# takujou_memo.net
KiCad netlist of a schematic drawn in EAGLE
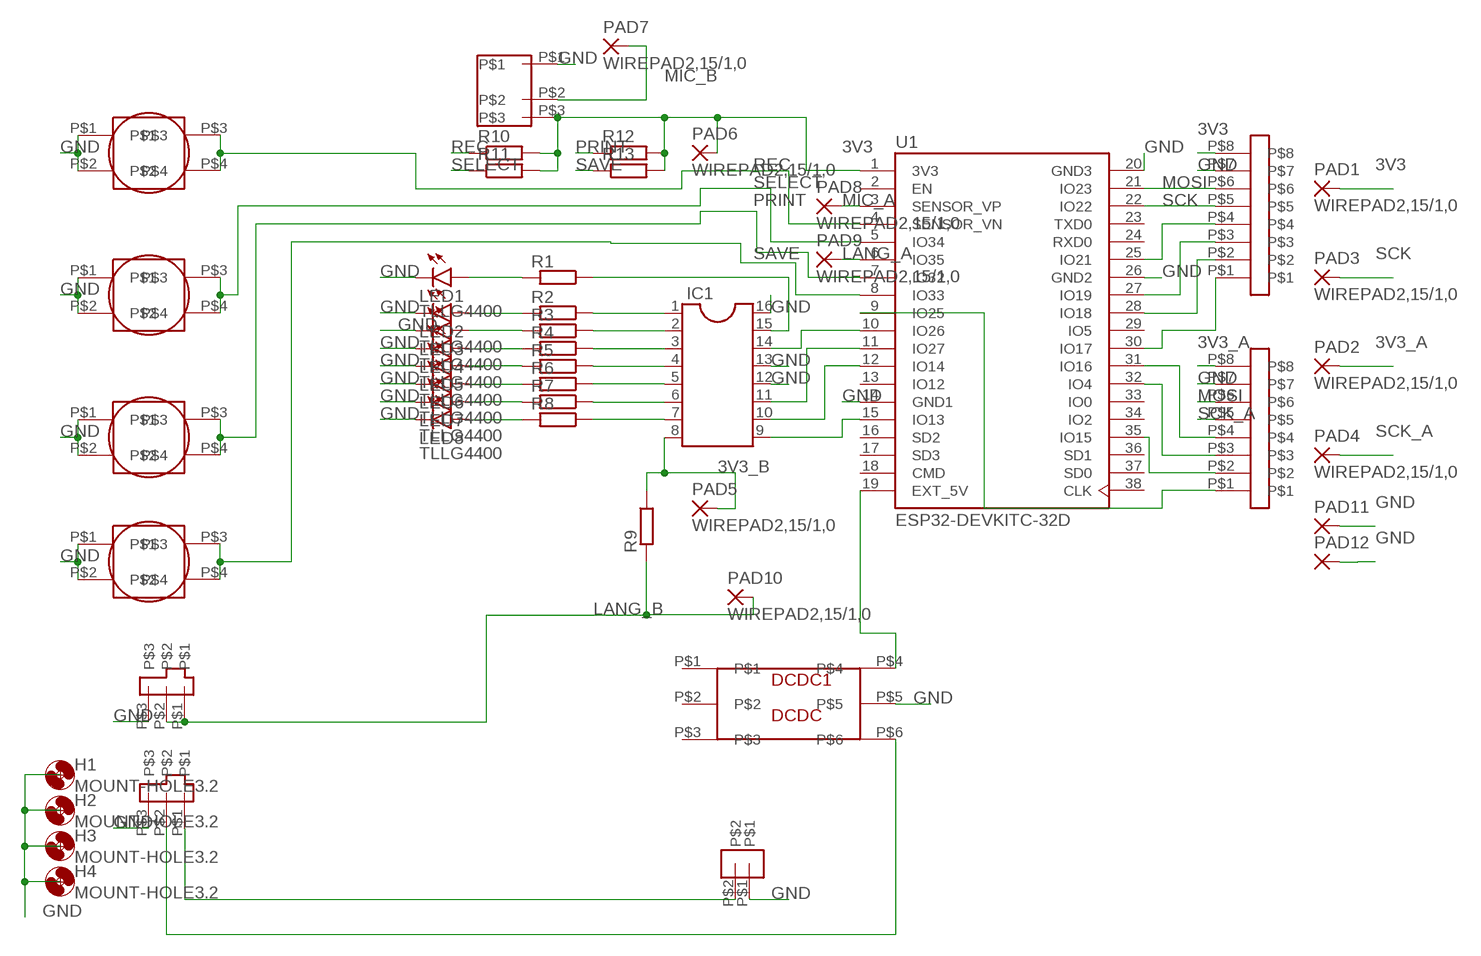
[diagram p0: schematic, sheet 1]

(export (version "E")
  (design (tool "Eeschema 10.0.6"))
  (components
    (comp (ref "BATTERY1")
      (value "BATTERY")
      (footprint "eagle-import:BATTERY")
      (libsource (lib "eagle-import") (part "BATTERY"))
    )
    (comp (ref "DCDC1")
      (value "DCDC")
      (footprint "eagle-import:DCDC")
      (libsource (lib "eagle-import") (part "DCDC"))
    )
    (comp (ref "DISPLAY1")
      (value "DISPLAY")
      (footprint "eagle-import:DISPLAY")
      (libsource (lib "eagle-import") (part "DISPLAY"))
    )
    (comp (ref "DISPLAY2")
      (value "DISPLAY")
      (footprint "eagle-import:DISPLAY")
      (libsource (lib "eagle-import") (part "DISPLAY"))
    )
    (comp (ref "H1")
      (value "MOUNT-HOLE3.2")
      (footprint "eagle-import:3,2")
      (libsource (lib "eagle-import") (part "MOUNT-HOLE3.2"))
    )
    (comp (ref "H2")
      (value "MOUNT-HOLE3.2")
      (footprint "eagle-import:3,2")
      (libsource (lib "eagle-import") (part "MOUNT-HOLE3.2"))
    )
    (comp (ref "H3")
      (value "MOUNT-HOLE3.2")
      (footprint "eagle-import:3,2")
      (libsource (lib "eagle-import") (part "MOUNT-HOLE3.2"))
    )
    (comp (ref "H4")
      (value "MOUNT-HOLE3.2")
      (footprint "eagle-import:3,2")
      (libsource (lib "eagle-import") (part "MOUNT-HOLE3.2"))
    )
    (comp (ref "IC1")
      (value "DIL16S")
      (footprint "eagle-import:SOCKET-16")
      (libsource (lib "eagle-import") (part "DIL16S"))
    )
    (comp (ref "LED1")
      (value "TLLG4400")
      (footprint "eagle-import:LED3MM")
      (fields (field (name "MF") "VISHAY SEMICONDUCTOR"))
      (libsource (lib "eagle-import") (part "TLLG4400"))
    )
    (comp (ref "LED2")
      (value "TLLG4400")
      (footprint "eagle-import:LED3MM")
      (fields (field (name "MF") "VISHAY SEMICONDUCTOR"))
      (libsource (lib "eagle-import") (part "TLLG4400"))
    )
    (comp (ref "LED3")
      (value "TLLG4400")
      (footprint "eagle-import:LED3MM")
      (fields (field (name "MF") "VISHAY SEMICONDUCTOR"))
      (libsource (lib "eagle-import") (part "TLLG4400"))
    )
    (comp (ref "LED4")
      (value "TLLG4400")
      (footprint "eagle-import:LED3MM")
      (fields (field (name "MF") "VISHAY SEMICONDUCTOR"))
      (libsource (lib "eagle-import") (part "TLLG4400"))
    )
    (comp (ref "LED5")
      (value "TLLG4400")
      (footprint "eagle-import:LED3MM")
      (fields (field (name "MF") "VISHAY SEMICONDUCTOR"))
      (libsource (lib "eagle-import") (part "TLLG4400"))
    )
    (comp (ref "LED6")
      (value "TLLG4400")
      (footprint "eagle-import:LED3MM")
      (fields (field (name "MF") "VISHAY SEMICONDUCTOR"))
      (libsource (lib "eagle-import") (part "TLLG4400"))
    )
    (comp (ref "LED7")
      (value "TLLG4400")
      (footprint "eagle-import:LED3MM")
      (fields (field (name "MF") "VISHAY SEMICONDUCTOR"))
      (libsource (lib "eagle-import") (part "TLLG4400"))
    )
    (comp (ref "LED8")
      (value "TLLG4400")
      (footprint "eagle-import:LED3MM")
      (fields (field (name "MF") "VISHAY SEMICONDUCTOR"))
      (libsource (lib "eagle-import") (part "TLLG4400"))
    )
    (comp (ref "MIC1")
      (value "MIC")
      (footprint "eagle-import:MIC")
      (libsource (lib "eagle-import") (part "MIC"))
    )
    (comp (ref "PAD1")
      (value "WIREPAD2,15/1,0")
      (footprint "eagle-import:2,15_1,0")
      (libsource (lib "eagle-import") (part "WIREPAD2,15/1,0"))
    )
    (comp (ref "PAD2")
      (value "WIREPAD2,15/1,0")
      (footprint "eagle-import:2,15_1,0")
      (libsource (lib "eagle-import") (part "WIREPAD2,15/1,0"))
    )
    (comp (ref "PAD3")
      (value "WIREPAD2,15/1,0")
      (footprint "eagle-import:2,15_1,0")
      (libsource (lib "eagle-import") (part "WIREPAD2,15/1,0"))
    )
    (comp (ref "PAD4")
      (value "WIREPAD2,15/1,0")
      (footprint "eagle-import:2,15_1,0")
      (libsource (lib "eagle-import") (part "WIREPAD2,15/1,0"))
    )
    (comp (ref "PAD5")
      (value "WIREPAD2,15/1,0")
      (footprint "eagle-import:2,15_1,0")
      (libsource (lib "eagle-import") (part "WIREPAD2,15/1,0"))
    )
    (comp (ref "PAD6")
      (value "WIREPAD2,15/1,0")
      (footprint "eagle-import:2,15_1,0")
      (libsource (lib "eagle-import") (part "WIREPAD2,15/1,0"))
    )
    (comp (ref "PAD7")
      (value "WIREPAD2,15/1,0")
      (footprint "eagle-import:2,15_1,0")
      (libsource (lib "eagle-import") (part "WIREPAD2,15/1,0"))
    )
    (comp (ref "PAD8")
      (value "WIREPAD2,15/1,0")
      (footprint "eagle-import:2,15_1,0")
      (libsource (lib "eagle-import") (part "WIREPAD2,15/1,0"))
    )
    (comp (ref "PAD9")
      (value "WIREPAD2,15/1,0")
      (footprint "eagle-import:2,15_1,0")
      (libsource (lib "eagle-import") (part "WIREPAD2,15/1,0"))
    )
    (comp (ref "PAD10")
      (value "WIREPAD2,15/1,0")
      (footprint "eagle-import:2,15_1,0")
      (libsource (lib "eagle-import") (part "WIREPAD2,15/1,0"))
    )
    (comp (ref "PAD11")
      (value "2,15/1,0")
      (footprint "eagle-import:2,15_1,0")
      (libsource (lib "eagle-import") (part "2,15/1,0"))
    )
    (comp (ref "PAD12")
      (value "2,15/1,0")
      (footprint "eagle-import:2,15_1,0")
      (libsource (lib "eagle-import") (part "2,15/1,0"))
    )
    (comp (ref "R1")
      (value "SMK")
      (footprint "eagle-import:SMK")
      (libsource (lib "eagle-import") (part "SMK"))
    )
    (comp (ref "R2")
      (value "SMK")
      (footprint "eagle-import:SMK")
      (libsource (lib "eagle-import") (part "SMK"))
    )
    (comp (ref "R3")
      (value "SMK")
      (footprint "eagle-import:SMK")
      (libsource (lib "eagle-import") (part "SMK"))
    )
    (comp (ref "R4")
      (value "SMK")
      (footprint "eagle-import:SMK")
      (libsource (lib "eagle-import") (part "SMK"))
    )
    (comp (ref "R5")
      (value "SMK")
      (footprint "eagle-import:SMK")
      (libsource (lib "eagle-import") (part "SMK"))
    )
    (comp (ref "R6")
      (value "SMK")
      (footprint "eagle-import:SMK")
      (libsource (lib "eagle-import") (part "SMK"))
    )
    (comp (ref "R7")
      (value "SMK")
      (footprint "eagle-import:SMK")
      (libsource (lib "eagle-import") (part "SMK"))
    )
    (comp (ref "R8")
      (value "SMK")
      (footprint "eagle-import:SMK")
      (libsource (lib "eagle-import") (part "SMK"))
    )
    (comp (ref "R9")
      (value "SMK")
      (footprint "eagle-import:SMK")
      (libsource (lib "eagle-import") (part "SMK"))
    )
    (comp (ref "R10")
      (value "R-EU_0207/10")
      (footprint "eagle-import:0207_10")
      (libsource (lib "eagle-import") (part "R-EU_0207/10"))
    )
    (comp (ref "R11")
      (value "R-EU_0207/10")
      (footprint "eagle-import:0207_10")
      (libsource (lib "eagle-import") (part "R-EU_0207/10"))
    )
    (comp (ref "R12")
      (value "R-EU_0207/10")
      (footprint "eagle-import:0207_10")
      (libsource (lib "eagle-import") (part "R-EU_0207/10"))
    )
    (comp (ref "R13")
      (value "R-EU_0207/10")
      (footprint "eagle-import:0207_10")
      (libsource (lib "eagle-import") (part "R-EU_0207/10"))
    )
    (comp (ref "SWITCH1")
      (value "SWITCH")
      (footprint "eagle-import:SWITCH")
      (libsource (lib "eagle-import") (part "SWITCH"))
    )
    (comp (ref "SWITCH2")
      (value "SWITCH")
      (footprint "eagle-import:SWITCH")
      (libsource (lib "eagle-import") (part "SWITCH"))
    )
    (comp (ref "SWITCH3")
      (value "SWITCH")
      (footprint "eagle-import:SWITCH")
      (libsource (lib "eagle-import") (part "SWITCH"))
    )
    (comp (ref "SWITCH4")
      (value "SWITCH")
      (footprint "eagle-import:SWITCH")
      (libsource (lib "eagle-import") (part "SWITCH"))
    )
    (comp (ref "TOGGLE1")
      (value "TOGGLE")
      (footprint "eagle-import:TOGGLE")
      (libsource (lib "eagle-import") (part "TOGGLE"))
    )
    (comp (ref "TOGGLE2")
      (value "TOGGLE")
      (footprint "eagle-import:TOGGLE")
      (libsource (lib "eagle-import") (part "TOGGLE"))
    )
    (comp (ref "U1")
      (value "ESP32-DEVKITC-32D")
      (footprint "eagle-import:MODULE_ESP32-DEVKITC-32D")
      (fields (field (name "MF") "Espressif Systems"))
      (libsource (lib "eagle-import") (part "ESP32-DEVKITC-32D"))
    )
  )
  (nets
    (net (code "1") (name "/3V3") (class "Default")
      (node (ref "DISPLAY1") (pin "P$8") (pinfunction "P$8_P$8") (pintype "bidirectional"))
      (node (ref "MIC1") (pin "P$3") (pinfunction "P$3_P$3") (pintype "bidirectional"))
      (node (ref "PAD1") (pin "1") (pinfunction "P_1") (pintype "passive"))
      (node (ref "PAD6") (pin "1") (pinfunction "P_1") (pintype "passive"))
      (node (ref "R10") (pin "2") (pinfunction "2_2") (pintype "passive"))
      (node (ref "R11") (pin "2") (pinfunction "2_2") (pintype "passive"))
      (node (ref "R12") (pin "2") (pinfunction "2_2") (pintype "passive"))
      (node (ref "R13") (pin "2") (pinfunction "2_2") (pintype "passive"))
      (node (ref "U1") (pin "1") (pinfunction "3V3_1") (pintype "power_in"))
    )
    (net (code "2") (name "/3V3_A") (class "Default")
      (node (ref "DISPLAY2") (pin "P$8") (pinfunction "P$8_P$8") (pintype "bidirectional"))
      (node (ref "PAD2") (pin "1") (pinfunction "P_1") (pintype "passive"))
    )
    (net (code "3") (name "/3V3_B") (class "Default")
      (node (ref "IC1") (pin "8") (pinfunction "8_8") (pintype "passive"))
      (node (ref "PAD5") (pin "1") (pinfunction "P_1") (pintype "passive"))
      (node (ref "R9") (pin "1") (pinfunction "1_1") (pintype "passive"))
    )
    (net (code "4") (name "/GND") (class "Default")
      (node (ref "BATTERY1") (pin "P$1") (pinfunction "P$1_P$1") (pintype "bidirectional"))
      (node (ref "DCDC1") (pin "P$5") (pinfunction "P$5_P$5") (pintype "bidirectional"))
      (node (ref "DISPLAY1") (pin "P$7") (pinfunction "P$7_P$7") (pintype "bidirectional"))
      (node (ref "DISPLAY2") (pin "P$7") (pinfunction "P$7_P$7") (pintype "bidirectional"))
      (node (ref "IC1") (pin "12") (pinfunction "12_12") (pintype "passive"))
      (node (ref "IC1") (pin "13") (pinfunction "13_13") (pintype "passive"))
      (node (ref "IC1") (pin "16") (pinfunction "16_16") (pintype "passive"))
      (node (ref "LED1") (pin "K") (pinfunction "C_K") (pintype "passive"))
      (node (ref "LED2") (pin "K") (pinfunction "C_K") (pintype "passive"))
      (node (ref "LED3") (pin "K") (pinfunction "C_K") (pintype "passive"))
      (node (ref "LED4") (pin "K") (pinfunction "C_K") (pintype "passive"))
      (node (ref "LED5") (pin "K") (pinfunction "C_K") (pintype "passive"))
      (node (ref "LED6") (pin "K") (pinfunction "C_K") (pintype "passive"))
      (node (ref "LED7") (pin "K") (pinfunction "C_K") (pintype "passive"))
      (node (ref "LED8") (pin "K") (pinfunction "C_K") (pintype "passive"))
      (node (ref "MIC1") (pin "P$1") (pinfunction "P$1_P$1") (pintype "bidirectional"))
      (node (ref "PAD11") (pin "1") (pinfunction "P_1") (pintype "passive"))
      (node (ref "PAD12") (pin "1") (pinfunction "P_1") (pintype "passive"))
      (node (ref "SWITCH1") (pin "P$1") (pinfunction "P$1_P$1") (pintype "bidirectional"))
      (node (ref "SWITCH1") (pin "P$2") (pinfunction "P$2_P$2") (pintype "bidirectional"))
      (node (ref "SWITCH2") (pin "P$1") (pinfunction "P$1_P$1") (pintype "bidirectional"))
      (node (ref "SWITCH2") (pin "P$2") (pinfunction "P$2_P$2") (pintype "bidirectional"))
      (node (ref "SWITCH3") (pin "P$1") (pinfunction "P$1_P$1") (pintype "bidirectional"))
      (node (ref "SWITCH3") (pin "P$2") (pinfunction "P$2_P$2") (pintype "bidirectional"))
      (node (ref "SWITCH4") (pin "P$1") (pinfunction "P$1_P$1") (pintype "bidirectional"))
      (node (ref "SWITCH4") (pin "P$2") (pinfunction "P$2_P$2") (pintype "bidirectional"))
      (node (ref "TOGGLE1") (pin "P$3") (pinfunction "P$3_P$3") (pintype "bidirectional"))
      (node (ref "TOGGLE2") (pin "P$3") (pinfunction "P$3_P$3") (pintype "bidirectional"))
      (node (ref "U1") (pin "14") (pinfunction "GND1_14") (pintype "power_in"))
      (node (ref "U1") (pin "20") (pinfunction "GND3_20") (pintype "power_in"))
      (node (ref "U1") (pin "26") (pinfunction "GND2_26") (pintype "power_in"))
    )
    (net (code "5") (name "/LANG_A") (class "Default")
      (node (ref "PAD9") (pin "1") (pinfunction "P_1") (pintype "passive"))
      (node (ref "U1") (pin "6") (pinfunction "IO35_6") (pintype "bidirectional"))
    )
    (net (code "6") (name "/LANG_B") (class "Default")
      (node (ref "PAD10") (pin "1") (pinfunction "P_1") (pintype "passive"))
      (node (ref "R9") (pin "2") (pinfunction "2_2") (pintype "passive"))
      (node (ref "TOGGLE1") (pin "P$1") (pinfunction "P$1_P$1") (pintype "bidirectional"))
      (node (ref "TOGGLE1") (pin "P$2") (pinfunction "P$2_P$2") (pintype "bidirectional"))
    )
    (net (code "7") (name "/MIC_A") (class "Default")
      (node (ref "PAD8") (pin "1") (pinfunction "P_1") (pintype "passive"))
      (node (ref "U1") (pin "3") (pinfunction "SENSOR_VP_3") (pintype "input"))
    )
    (net (code "8") (name "/MIC_B") (class "Default")
      (node (ref "MIC1") (pin "P$2") (pinfunction "P$2_P$2") (pintype "bidirectional"))
      (node (ref "PAD7") (pin "1") (pinfunction "P_1") (pintype "passive"))
    )
    (net (code "9") (name "/MOSI") (class "Default")
      (node (ref "DISPLAY1") (pin "P$6") (pinfunction "P$6_P$6") (pintype "bidirectional"))
      (node (ref "DISPLAY2") (pin "P$6") (pinfunction "P$6_P$6") (pintype "bidirectional"))
      (node (ref "U1") (pin "21") (pinfunction "IO23_21") (pintype "bidirectional"))
    )
    (net (code "10") (name "/PRINT") (class "Default")
      (node (ref "R12") (pin "1") (pinfunction "1_1") (pintype "passive"))
      (node (ref "SWITCH3") (pin "P$3") (pinfunction "P$3_P$3") (pintype "bidirectional"))
      (node (ref "SWITCH3") (pin "P$4") (pinfunction "P$4_P$4") (pintype "bidirectional"))
      (node (ref "U1") (pin "7") (pinfunction "IO32_7") (pintype "bidirectional"))
    )
    (net (code "11") (name "/REC") (class "Default")
      (node (ref "R10") (pin "1") (pinfunction "1_1") (pintype "passive"))
      (node (ref "SWITCH1") (pin "P$3") (pinfunction "P$3_P$3") (pintype "bidirectional"))
      (node (ref "SWITCH1") (pin "P$4") (pinfunction "P$4_P$4") (pintype "bidirectional"))
      (node (ref "U1") (pin "4") (pinfunction "SENSOR_VN_4") (pintype "input"))
    )
    (net (code "12") (name "/SAVE") (class "Default")
      (node (ref "R13") (pin "1") (pinfunction "1_1") (pintype "passive"))
      (node (ref "SWITCH4") (pin "P$3") (pinfunction "P$3_P$3") (pintype "bidirectional"))
      (node (ref "SWITCH4") (pin "P$4") (pinfunction "P$4_P$4") (pintype "bidirectional"))
      (node (ref "U1") (pin "8") (pinfunction "IO33_8") (pintype "bidirectional"))
    )
    (net (code "13") (name "/SCK") (class "Default")
      (node (ref "DISPLAY1") (pin "P$5") (pinfunction "P$5_P$5") (pintype "bidirectional"))
      (node (ref "PAD3") (pin "1") (pinfunction "P_1") (pintype "passive"))
      (node (ref "U1") (pin "22") (pinfunction "IO22_22") (pintype "bidirectional"))
    )
    (net (code "14") (name "/SCK_A") (class "Default")
      (node (ref "DISPLAY2") (pin "P$5") (pinfunction "P$5_P$5") (pintype "bidirectional"))
      (node (ref "PAD4") (pin "1") (pinfunction "P_1") (pintype "passive"))
    )
    (net (code "15") (name "/SELECT") (class "Default")
      (node (ref "R11") (pin "1") (pinfunction "1_1") (pintype "passive"))
      (node (ref "SWITCH2") (pin "P$3") (pinfunction "P$3_P$3") (pintype "bidirectional"))
      (node (ref "SWITCH2") (pin "P$4") (pinfunction "P$4_P$4") (pintype "bidirectional"))
      (node (ref "U1") (pin "5") (pinfunction "IO34_5") (pintype "bidirectional"))
    )
    (net (code "16") (name "Net-(BATTERY1-PadP$2)") (class "Default")
      (node (ref "BATTERY1") (pin "P$2") (pinfunction "P$2_P$2") (pintype "bidirectional"))
      (node (ref "TOGGLE2") (pin "P$1") (pinfunction "P$1_P$1") (pintype "bidirectional"))
    )
    (net (code "17") (name "Net-(DCDC1-PadP$6)") (class "Default")
      (node (ref "DCDC1") (pin "P$6") (pinfunction "P$6_P$6") (pintype "bidirectional"))
      (node (ref "TOGGLE2") (pin "P$2") (pinfunction "P$2_P$2") (pintype "bidirectional"))
    )
    (net (code "18") (name "Net-(IC1-Pad1)") (class "Default")
      (node (ref "IC1") (pin "1") (pinfunction "1_1") (pintype "passive"))
      (node (ref "R2") (pin "1") (pinfunction "1_1") (pintype "passive"))
    )
    (net (code "19") (name "Net-(IC1-Pad2)") (class "Default")
      (node (ref "IC1") (pin "2") (pinfunction "2_2") (pintype "passive"))
      (node (ref "R3") (pin "1") (pinfunction "1_1") (pintype "passive"))
    )
    (net (code "20") (name "Net-(IC1-Pad3)") (class "Default")
      (node (ref "IC1") (pin "3") (pinfunction "3_3") (pintype "passive"))
      (node (ref "R4") (pin "1") (pinfunction "1_1") (pintype "passive"))
    )
    (net (code "21") (name "Net-(IC1-Pad4)") (class "Default")
      (node (ref "IC1") (pin "4") (pinfunction "4_4") (pintype "passive"))
      (node (ref "R5") (pin "1") (pinfunction "1_1") (pintype "passive"))
    )
    (net (code "22") (name "Net-(IC1-Pad5)") (class "Default")
      (node (ref "IC1") (pin "5") (pinfunction "5_5") (pintype "passive"))
      (node (ref "R6") (pin "1") (pinfunction "1_1") (pintype "passive"))
    )
    (net (code "23") (name "Net-(IC1-Pad6)") (class "Default")
      (node (ref "IC1") (pin "6") (pinfunction "6_6") (pintype "passive"))
      (node (ref "R7") (pin "1") (pinfunction "1_1") (pintype "passive"))
    )
    (net (code "24") (name "Net-(IC1-Pad7)") (class "Default")
      (node (ref "IC1") (pin "7") (pinfunction "7_7") (pintype "passive"))
      (node (ref "R8") (pin "1") (pinfunction "1_1") (pintype "passive"))
    )
    (net (code "25") (name "Net-(IC1-Pad15)") (class "Default")
      (node (ref "IC1") (pin "15") (pinfunction "15_15") (pintype "passive"))
      (node (ref "R1") (pin "1") (pinfunction "1_1") (pintype "passive"))
    )
    (net (code "26") (name "Net-(LED1-PadA)") (class "Default")
      (node (ref "LED1") (pin "A") (pinfunction "A_A") (pintype "passive"))
      (node (ref "R1") (pin "2") (pinfunction "2_2") (pintype "passive"))
    )
    (net (code "27") (name "Net-(LED2-PadA)") (class "Default")
      (node (ref "LED2") (pin "A") (pinfunction "A_A") (pintype "passive"))
      (node (ref "R2") (pin "2") (pinfunction "2_2") (pintype "passive"))
    )
    (net (code "28") (name "Net-(LED3-PadA)") (class "Default")
      (node (ref "LED3") (pin "A") (pinfunction "A_A") (pintype "passive"))
      (node (ref "R3") (pin "2") (pinfunction "2_2") (pintype "passive"))
    )
    (net (code "29") (name "Net-(LED4-PadA)") (class "Default")
      (node (ref "LED4") (pin "A") (pinfunction "A_A") (pintype "passive"))
      (node (ref "R4") (pin "2") (pinfunction "2_2") (pintype "passive"))
    )
    (net (code "30") (name "Net-(LED5-PadA)") (class "Default")
      (node (ref "LED5") (pin "A") (pinfunction "A_A") (pintype "passive"))
      (node (ref "R5") (pin "2") (pinfunction "2_2") (pintype "passive"))
    )
    (net (code "31") (name "Net-(LED6-PadA)") (class "Default")
      (node (ref "LED6") (pin "A") (pinfunction "A_A") (pintype "passive"))
      (node (ref "R6") (pin "2") (pinfunction "2_2") (pintype "passive"))
    )
    (net (code "32") (name "Net-(LED7-PadA)") (class "Default")
      (node (ref "LED7") (pin "A") (pinfunction "A_A") (pintype "passive"))
      (node (ref "R7") (pin "2") (pinfunction "2_2") (pintype "passive"))
    )
    (net (code "33") (name "Net-(LED8-PadA)") (class "Default")
      (node (ref "LED8") (pin "A") (pinfunction "A_A") (pintype "passive"))
      (node (ref "R8") (pin "2") (pinfunction "2_2") (pintype "passive"))
    )
    (net (code "34") (name "Net-(U1-EXT_5V)") (class "Default")
      (node (ref "DCDC1") (pin "P$4") (pinfunction "P$4_P$4") (pintype "bidirectional"))
      (node (ref "U1") (pin "19") (pinfunction "EXT_5V_19") (pintype "power_in"))
    )
    (net (code "35") (name "Net-(U1-IO4)") (class "Default")
      (node (ref "DISPLAY2") (pin "P$3") (pinfunction "P$3_P$3") (pintype "bidirectional"))
      (node (ref "U1") (pin "32") (pinfunction "IO4_32") (pintype "bidirectional"))
    )
    (net (code "36") (name "Net-(U1-IO13)") (class "Default")
      (node (ref "IC1") (pin "9") (pinfunction "9_9") (pintype "passive"))
      (node (ref "U1") (pin "15") (pinfunction "IO13_15") (pintype "bidirectional"))
    )
    (net (code "37") (name "Net-(U1-IO14)") (class "Default")
      (node (ref "IC1") (pin "10") (pinfunction "10_10") (pintype "passive"))
      (node (ref "U1") (pin "12") (pinfunction "IO14_12") (pintype "bidirectional"))
    )
    (net (code "38") (name "Net-(U1-IO15)") (class "Default")
      (node (ref "DISPLAY2") (pin "P$2") (pinfunction "P$2_P$2") (pintype "bidirectional"))
      (node (ref "U1") (pin "35") (pinfunction "IO15_35") (pintype "bidirectional"))
    )
    (net (code "39") (name "Net-(U1-IO16)") (class "Default")
      (node (ref "DISPLAY2") (pin "P$4") (pinfunction "P$4_P$4") (pintype "bidirectional"))
      (node (ref "U1") (pin "31") (pinfunction "IO16_31") (pintype "bidirectional"))
    )
    (net (code "40") (name "Net-(U1-IO17)") (class "Default")
      (node (ref "DISPLAY1") (pin "P$1") (pinfunction "P$1_P$1") (pintype "bidirectional"))
      (node (ref "U1") (pin "30") (pinfunction "IO17_30") (pintype "bidirectional"))
    )
    (net (code "41") (name "Net-(U1-IO18)") (class "Default")
      (node (ref "DISPLAY1") (pin "P$2") (pinfunction "P$2_P$2") (pintype "bidirectional"))
      (node (ref "U1") (pin "28") (pinfunction "IO18_28") (pintype "bidirectional"))
    )
    (net (code "42") (name "Net-(U1-IO19)") (class "Default")
      (node (ref "DISPLAY1") (pin "P$3") (pinfunction "P$3_P$3") (pintype "bidirectional"))
      (node (ref "U1") (pin "27") (pinfunction "IO19_27") (pintype "bidirectional"))
    )
    (net (code "43") (name "Net-(U1-IO21)") (class "Default")
      (node (ref "DISPLAY1") (pin "P$4") (pinfunction "P$4_P$4") (pintype "bidirectional"))
      (node (ref "U1") (pin "25") (pinfunction "IO21_25") (pintype "bidirectional"))
    )
    (net (code "44") (name "Net-(U1-IO25)") (class "Default")
      (node (ref "DISPLAY2") (pin "P$1") (pinfunction "P$1_P$1") (pintype "bidirectional"))
      (node (ref "U1") (pin "9") (pinfunction "IO25_9") (pintype "bidirectional"))
    )
    (net (code "45") (name "Net-(U1-IO26)") (class "Default")
      (node (ref "IC1") (pin "14") (pinfunction "14_14") (pintype "passive"))
      (node (ref "U1") (pin "10") (pinfunction "IO26_10") (pintype "bidirectional"))
    )
    (net (code "46") (name "Net-(U1-IO27)") (class "Default")
      (node (ref "IC1") (pin "11") (pinfunction "11_11") (pintype "passive"))
      (node (ref "U1") (pin "11") (pinfunction "IO27_11") (pintype "bidirectional"))
    )
    (net (code "47") (name "unconnected-(DCDC1-PadP$1)") (class "Default")
      (node (ref "DCDC1") (pin "P$1") (pinfunction "P$1_P$1") (pintype "bidirectional"))
    )
    (net (code "48") (name "unconnected-(DCDC1-PadP$2)") (class "Default")
      (node (ref "DCDC1") (pin "P$2") (pinfunction "P$2_P$2") (pintype "bidirectional"))
    )
    (net (code "49") (name "unconnected-(DCDC1-PadP$3)") (class "Default")
      (node (ref "DCDC1") (pin "P$3") (pinfunction "P$3_P$3") (pintype "bidirectional"))
    )
    (net (code "50") (name "unconnected-(U1-CLK-Pad38)") (class "Default")
      (node (ref "U1") (pin "38") (pinfunction "CLK_38") (pintype "input"))
    )
    (net (code "51") (name "unconnected-(U1-CMD-Pad18)") (class "Default")
      (node (ref "U1") (pin "18") (pinfunction "CMD_18") (pintype "bidirectional"))
    )
    (net (code "52") (name "unconnected-(U1-EN-Pad2)") (class "Default")
      (node (ref "U1") (pin "2") (pinfunction "EN_2") (pintype "input"))
    )
    (net (code "53") (name "unconnected-(U1-IO0-Pad33)") (class "Default")
      (node (ref "U1") (pin "33") (pinfunction "IO0_33") (pintype "bidirectional"))
    )
    (net (code "54") (name "unconnected-(U1-IO2-Pad34)") (class "Default")
      (node (ref "U1") (pin "34") (pinfunction "IO2_34") (pintype "bidirectional"))
    )
    (net (code "55") (name "unconnected-(U1-IO5-Pad29)") (class "Default")
      (node (ref "U1") (pin "29") (pinfunction "IO5_29") (pintype "bidirectional"))
    )
    (net (code "56") (name "unconnected-(U1-IO12-Pad13)") (class "Default")
      (node (ref "U1") (pin "13") (pinfunction "IO12_13") (pintype "bidirectional"))
    )
    (net (code "57") (name "unconnected-(U1-RXD0-Pad24)") (class "Default")
      (node (ref "U1") (pin "24") (pinfunction "RXD0_24") (pintype "input"))
    )
    (net (code "58") (name "unconnected-(U1-SD0-Pad37)") (class "Default")
      (node (ref "U1") (pin "37") (pinfunction "SD0_37") (pintype "bidirectional"))
    )
    (net (code "59") (name "unconnected-(U1-SD1-Pad36)") (class "Default")
      (node (ref "U1") (pin "36") (pinfunction "SD1_36") (pintype "bidirectional"))
    )
    (net (code "60") (name "unconnected-(U1-SD2-Pad16)") (class "Default")
      (node (ref "U1") (pin "16") (pinfunction "SD2_16") (pintype "bidirectional"))
    )
    (net (code "61") (name "unconnected-(U1-SD3-Pad17)") (class "Default")
      (node (ref "U1") (pin "17") (pinfunction "SD3_17") (pintype "bidirectional"))
    )
    (net (code "62") (name "unconnected-(U1-TXD0-Pad23)") (class "Default")
      (node (ref "U1") (pin "23") (pinfunction "TXD0_23") (pintype "output"))
    )
  )
)
